# ModulationAnalog.net
KiCad netlist of a schematic drawn in Altium Designer
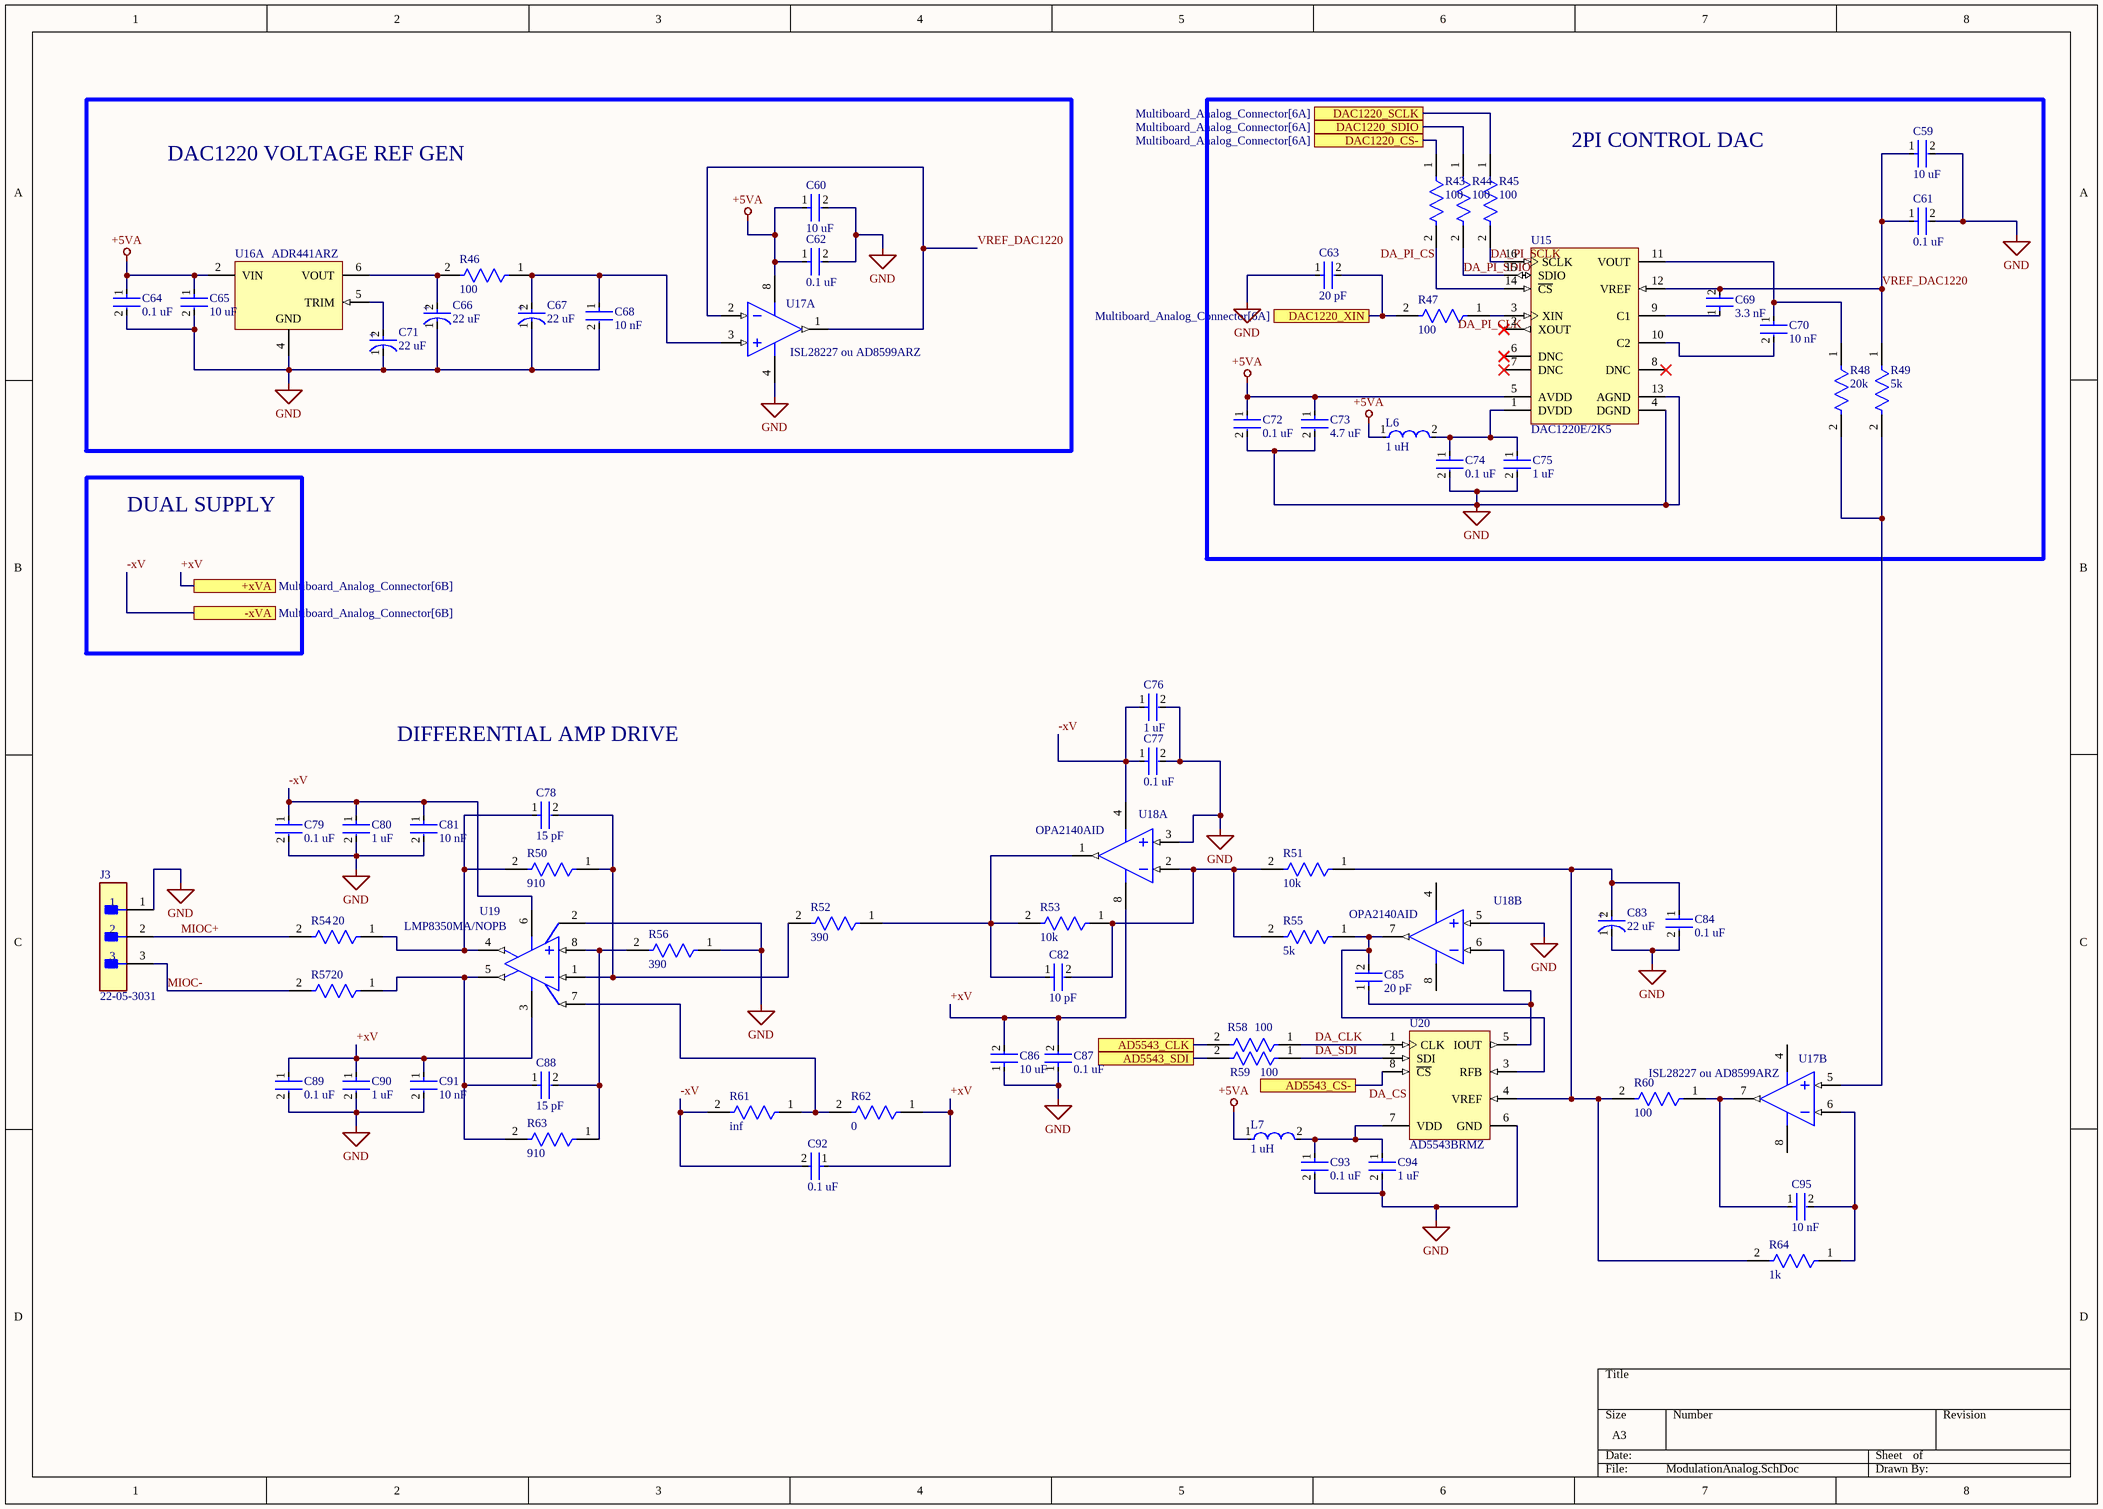
[diagram p0: ModulationAnalog.SchDoc]

(export (version "E")
  (design (tool "Eeschema 10.0.6"))
  (components
    (comp (ref "C59")
      (value "10 uF")
      (footprint "FP-CC0805-0_85-MFG")
      (description "CAP CER 0.1UF 25V X7R 0805")
      (fields (field (name "MANUFACTURER PART NUMBER") "CC0805KRX7R8BB104") (field (name "TOLERANCE") "0.1"))
      (libsource (lib "Altium Content Vault") (part "11868f565c42a9108669ba33697ecf6"))
    )
    (comp (ref "C60")
      (value "10 uF")
      (footprint "FP-CC0805-0_85-MFG")
      (description "CAP CER 0.1UF 25V X7R 0805")
      (fields (field (name "MANUFACTURER PART NUMBER") "CC0805KRX7R8BB104") (field (name "TOLERANCE") "0.1"))
      (libsource (lib "Altium Content Vault") (part "11868f565c42a9108669ba33697ecf6"))
    )
    (comp (ref "C61")
      (value "0.1 uF")
      (footprint "FP-CC0805-0_85-MFG")
      (description "CAP CER 0.1UF 25V X7R 0805")
      (fields (field (name "MANUFACTURER PART NUMBER") "CC0805KRX7R8BB104") (field (name "TOLERANCE") "0.1"))
      (libsource (lib "Altium Content Vault") (part "11868f565c42a9108669ba33697ecf6"))
    )
    (comp (ref "C62")
      (value "0.1 uF")
      (footprint "FP-CC0805-0_85-MFG")
      (description "CAP CER 0.1UF 25V X7R 0805")
      (fields (field (name "MANUFACTURER PART NUMBER") "CC0805KRX7R8BB104") (field (name "TOLERANCE") "0.1"))
      (libsource (lib "Altium Content Vault") (part "11868f565c42a9108669ba33697ecf6"))
    )
    (comp (ref "C63")
      (value "20 pF")
      (footprint "FP-CC0805-0_85-MFG")
      (description "CAP CER 0.1UF 25V X7R 0805")
      (fields (field (name "MANUFACTURER PART NUMBER") "CC0805KRX7R8BB104") (field (name "TOLERANCE") "0.1"))
      (libsource (lib "Altium Content Vault") (part "11868f565c42a9108669ba33697ecf6"))
    )
    (comp (ref "C64")
      (value "0.1 uF")
      (footprint "FP-CC0805-0_85-MFG")
      (description "CAP CER 0.1UF 25V X7R 0805")
      (fields (field (name "MANUFACTURER PART NUMBER") "CC0805KRX7R8BB104") (field (name "TOLERANCE") "0.1"))
      (libsource (lib "Altium Content Vault") (part "11868f565c42a9108669ba33697ecf6"))
    )
    (comp (ref "C65")
      (value "10 uF")
      (footprint "FP-CC0805-0_85-MFG")
      (description "CAP CER 0.1UF 25V X7R 0805")
      (fields (field (name "MANUFACTURER PART NUMBER") "CC0805KRX7R8BB104") (field (name "TOLERANCE") "0.1"))
      (libsource (lib "Altium Content Vault") (part "11868f565c42a9108669ba33697ecf6"))
    )
    (comp (ref "C66")
      (value "22 uF")
      (footprint "FP-TAJP-MFG")
      (description "10uF 10V  ±20% 6Ω 0805  SMD Tantalum Capacitor")
      (fields (field (name "TOLERANCE") "20%") (field (name "VOLTAGE") "10V"))
      (libsource (lib "Altium Content Vault") (part "a00bbbee19879c290e62620ae7e47b1"))
    )
    (comp (ref "C67")
      (value "22 uF")
      (footprint "FP-TAJP-MFG")
      (description "10uF 10V  ±20% 6Ω 0805  SMD Tantalum Capacitor")
      (fields (field (name "TOLERANCE") "20%") (field (name "VOLTAGE") "10V"))
      (libsource (lib "Altium Content Vault") (part "a00bbbee19879c290e62620ae7e47b1"))
    )
    (comp (ref "C68")
      (value "10 nF")
      (footprint "FP-CC0805-0_85-MFG")
      (description "CAP CER 0.1UF 25V X7R 0805")
      (fields (field (name "MANUFACTURER PART NUMBER") "CC0805KRX7R8BB104") (field (name "TOLERANCE") "0.1"))
      (libsource (lib "Altium Content Vault") (part "11868f565c42a9108669ba33697ecf6"))
    )
    (comp (ref "C69")
      (value "3.3 nF")
      (footprint "FP-CC0805-0_85-MFG")
      (description "CAP CER 0.1UF 25V X7R 0805")
      (fields (field (name "MANUFACTURER PART NUMBER") "CC0805KRX7R8BB104") (field (name "TOLERANCE") "0.1"))
      (libsource (lib "Altium Content Vault") (part "11868f565c42a9108669ba33697ecf6"))
    )
    (comp (ref "C70")
      (value "10 nF")
      (footprint "FP-CC0805-0_85-MFG")
      (description "CAP CER 0.1UF 25V X7R 0805")
      (fields (field (name "MANUFACTURER PART NUMBER") "CC0805KRX7R8BB104") (field (name "TOLERANCE") "0.1"))
      (libsource (lib "Altium Content Vault") (part "11868f565c42a9108669ba33697ecf6"))
    )
    (comp (ref "C71")
      (value "22 uF")
      (footprint "FP-TAJP-MFG")
      (description "10uF 10V  ±20% 6Ω 0805  SMD Tantalum Capacitor")
      (fields (field (name "TOLERANCE") "20%") (field (name "VOLTAGE") "10V"))
      (libsource (lib "Altium Content Vault") (part "a00bbbee19879c290e62620ae7e47b1"))
    )
    (comp (ref "C72")
      (value "0.1 uF")
      (footprint "FP-CC0805-0_85-MFG")
      (description "CAP CER 0.1UF 25V X7R 0805")
      (fields (field (name "MANUFACTURER PART NUMBER") "CC0805KRX7R8BB104") (field (name "TOLERANCE") "0.1"))
      (libsource (lib "Altium Content Vault") (part "11868f565c42a9108669ba33697ecf6"))
    )
    (comp (ref "C73")
      (value "4.7 uF")
      (footprint "FP-CC0805-0_85-MFG")
      (description "CAP CER 0.1UF 25V X7R 0805")
      (fields (field (name "MANUFACTURER PART NUMBER") "CC0805KRX7R8BB104") (field (name "TOLERANCE") "0.1"))
      (libsource (lib "Altium Content Vault") (part "11868f565c42a9108669ba33697ecf6"))
    )
    (comp (ref "C74")
      (value "0.1 uF")
      (footprint "FP-CC0805-0_85-MFG")
      (description "CAP CER 0.1UF 25V X7R 0805")
      (fields (field (name "MANUFACTURER PART NUMBER") "CC0805KRX7R8BB104") (field (name "TOLERANCE") "0.1"))
      (libsource (lib "Altium Content Vault") (part "11868f565c42a9108669ba33697ecf6"))
    )
    (comp (ref "C75")
      (value "1 uF")
      (footprint "FP-CC0805-0_85-MFG")
      (description "CAP CER 0.1UF 25V X7R 0805")
      (fields (field (name "MANUFACTURER PART NUMBER") "CC0805KRX7R8BB104") (field (name "TOLERANCE") "0.1"))
      (libsource (lib "Altium Content Vault") (part "11868f565c42a9108669ba33697ecf6"))
    )
    (comp (ref "C76")
      (value "1 uF")
      (footprint "FP-CC0805-0_85-MFG")
      (description "CAP CER 0.1UF 25V X7R 0805")
      (fields (field (name "MANUFACTURER PART NUMBER") "CC0805KRX7R8BB104") (field (name "TOLERANCE") "0.1"))
      (libsource (lib "Altium Content Vault") (part "11868f565c42a9108669ba33697ecf6"))
    )
    (comp (ref "C77")
      (value "0.1 uF")
      (footprint "FP-CC0805-0_85-MFG")
      (description "CAP CER 0.1UF 25V X7R 0805")
      (fields (field (name "MANUFACTURER PART NUMBER") "CC0805KRX7R8BB104") (field (name "TOLERANCE") "0.1"))
      (libsource (lib "Altium Content Vault") (part "11868f565c42a9108669ba33697ecf6"))
    )
    (comp (ref "C78")
      (value "15 pF")
      (footprint "FP-CC0805-0_85-MFG")
      (description "CAP CER 0.1UF 25V X7R 0805")
      (fields (field (name "MANUFACTURER PART NUMBER") "CC0805KRX7R8BB104") (field (name "TOLERANCE") "0.1"))
      (libsource (lib "Altium Content Vault") (part "11868f565c42a9108669ba33697ecf6"))
    )
    (comp (ref "C79")
      (value "0.1 uF")
      (footprint "FP-CC0805-0_85-MFG")
      (description "CAP CER 0.1UF 25V X7R 0805")
      (fields (field (name "MANUFACTURER PART NUMBER") "CC0805KRX7R8BB104") (field (name "TOLERANCE") "0.1"))
      (libsource (lib "Altium Content Vault") (part "11868f565c42a9108669ba33697ecf6"))
    )
    (comp (ref "C80")
      (value "1 uF")
      (footprint "FP-CC0805-0_85-MFG")
      (description "CAP CER 0.1UF 25V X7R 0805")
      (fields (field (name "MANUFACTURER PART NUMBER") "CC0805KRX7R8BB104") (field (name "TOLERANCE") "0.1"))
      (libsource (lib "Altium Content Vault") (part "11868f565c42a9108669ba33697ecf6"))
    )
    (comp (ref "C81")
      (value "10 nF")
      (footprint "FP-CC0805-0_85-MFG")
      (description "CAP CER 0.1UF 25V X7R 0805")
      (fields (field (name "MANUFACTURER PART NUMBER") "CC0805KRX7R8BB104") (field (name "TOLERANCE") "0.1"))
      (libsource (lib "Altium Content Vault") (part "11868f565c42a9108669ba33697ecf6"))
    )
    (comp (ref "C82")
      (value "10 pF")
      (footprint "FP-CC0805-0_85-MFG")
      (description "CAP CER 0.1UF 25V X7R 0805")
      (fields (field (name "MANUFACTURER PART NUMBER") "CC0805KRX7R8BB104") (field (name "TOLERANCE") "0.1"))
      (libsource (lib "Altium Content Vault") (part "11868f565c42a9108669ba33697ecf6"))
    )
    (comp (ref "C83")
      (value "22 uF")
      (footprint "FP-TAJP-MFG")
      (description "10uF 10V  ±20% 6Ω 0805  SMD Tantalum Capacitor")
      (fields (field (name "TOLERANCE") "20%") (field (name "VOLTAGE") "10V"))
      (libsource (lib "Altium Content Vault") (part "a00bbbee19879c290e62620ae7e47b1"))
    )
    (comp (ref "C84")
      (value "0.1 uF")
      (footprint "FP-CC0805-0_85-MFG")
      (description "CAP CER 0.1UF 25V X7R 0805")
      (fields (field (name "MANUFACTURER PART NUMBER") "CC0805KRX7R8BB104") (field (name "TOLERANCE") "0.1"))
      (libsource (lib "Altium Content Vault") (part "11868f565c42a9108669ba33697ecf6"))
    )
    (comp (ref "C85")
      (value "20 pF")
      (footprint "FP-CC0805-0_85-MFG")
      (description "CAP CER 0.1UF 25V X7R 0805")
      (fields (field (name "MANUFACTURER PART NUMBER") "CC0805KRX7R8BB104") (field (name "TOLERANCE") "0.1"))
      (libsource (lib "Altium Content Vault") (part "11868f565c42a9108669ba33697ecf6"))
    )
    (comp (ref "C86")
      (value "10 uF")
      (footprint "FP-CC0805-0_85-MFG")
      (description "CAP CER 0.1UF 25V X7R 0805")
      (fields (field (name "MANUFACTURER PART NUMBER") "CC0805KRX7R8BB104") (field (name "TOLERANCE") "0.1"))
      (libsource (lib "Altium Content Vault") (part "11868f565c42a9108669ba33697ecf6"))
    )
    (comp (ref "C87")
      (value "0.1 uF")
      (footprint "FP-CC0805-0_85-MFG")
      (description "CAP CER 0.1UF 25V X7R 0805")
      (fields (field (name "MANUFACTURER PART NUMBER") "CC0805KRX7R8BB104") (field (name "TOLERANCE") "0.1"))
      (libsource (lib "Altium Content Vault") (part "11868f565c42a9108669ba33697ecf6"))
    )
    (comp (ref "C88")
      (value "15 pF")
      (footprint "FP-CC0805-0_85-MFG")
      (description "CAP CER 0.1UF 25V X7R 0805")
      (fields (field (name "MANUFACTURER PART NUMBER") "CC0805KRX7R8BB104") (field (name "TOLERANCE") "0.1"))
      (libsource (lib "Altium Content Vault") (part "11868f565c42a9108669ba33697ecf6"))
    )
    (comp (ref "C89")
      (value "0.1 uF")
      (footprint "FP-CC0805-0_85-MFG")
      (description "CAP CER 0.1UF 25V X7R 0805")
      (fields (field (name "MANUFACTURER PART NUMBER") "CC0805KRX7R8BB104") (field (name "TOLERANCE") "0.1"))
      (libsource (lib "Altium Content Vault") (part "11868f565c42a9108669ba33697ecf6"))
    )
    (comp (ref "C90")
      (value "1 uF")
      (footprint "FP-CC0805-0_85-MFG")
      (description "CAP CER 0.1UF 25V X7R 0805")
      (fields (field (name "MANUFACTURER PART NUMBER") "CC0805KRX7R8BB104") (field (name "TOLERANCE") "0.1"))
      (libsource (lib "Altium Content Vault") (part "11868f565c42a9108669ba33697ecf6"))
    )
    (comp (ref "C91")
      (value "10 nF")
      (footprint "FP-CC0805-0_85-MFG")
      (description "CAP CER 0.1UF 25V X7R 0805")
      (fields (field (name "MANUFACTURER PART NUMBER") "CC0805KRX7R8BB104") (field (name "TOLERANCE") "0.1"))
      (libsource (lib "Altium Content Vault") (part "11868f565c42a9108669ba33697ecf6"))
    )
    (comp (ref "C92")
      (value "0.1 uF")
      (footprint "FP-CC0805-0_85-MFG")
      (description "CAP CER 0.1UF 25V X7R 0805")
      (fields (field (name "MANUFACTURER PART NUMBER") "CC0805KRX7R8BB104") (field (name "TOLERANCE") "0.1"))
      (libsource (lib "Altium Content Vault") (part "11868f565c42a9108669ba33697ecf6"))
    )
    (comp (ref "C93")
      (value "0.1 uF")
      (footprint "FP-CC0805-0_85-MFG")
      (description "CAP CER 0.1UF 25V X7R 0805")
      (fields (field (name "MANUFACTURER PART NUMBER") "CC0805KRX7R8BB104") (field (name "TOLERANCE") "0.1"))
      (libsource (lib "Altium Content Vault") (part "11868f565c42a9108669ba33697ecf6"))
    )
    (comp (ref "C94")
      (value "1 uF")
      (footprint "FP-CC0805-0_85-MFG")
      (description "CAP CER 0.1UF 25V X7R 0805")
      (fields (field (name "MANUFACTURER PART NUMBER") "CC0805KRX7R8BB104") (field (name "TOLERANCE") "0.1"))
      (libsource (lib "Altium Content Vault") (part "11868f565c42a9108669ba33697ecf6"))
    )
    (comp (ref "C95")
      (value "10 nF")
      (footprint "FP-CC0805-0_85-MFG")
      (description "CAP CER 0.1UF 25V X7R 0805")
      (fields (field (name "MANUFACTURER PART NUMBER") "CC0805KRX7R8BB104") (field (name "TOLERANCE") "0.1"))
      (libsource (lib "Altium Content Vault") (part "11868f565c42a9108669ba33697ecf6"))
    )
    (comp (ref "J3")
      (value "22-05-3031")
      (footprint "FP-22-05-3031-MFG")
      (description "CONN HEADER R/A 3POS 2.54MM")
      (libsource (lib "Altium Content Vault") (part "0d3f023dd272f625e17a2be33dea85f"))
    )
    (comp (ref "L6")
      (value "1 uH")
      (footprint "FP-LQM21DN_00-IPC_B")
      (description "Multilayer Type Inductor for General Circuits, 0805 (2012), 1μH, 10%, 0.4Ω, 50mA")
      (fields (field (name "TOLERANCE") "10%"))
      (libsource (lib "Altium Content Vault") (part "725321dda6339637d4d059423bc1c3c"))
    )
    (comp (ref "L7")
      (value "1 uH")
      (footprint "FP-LQM21DN_00-IPC_B")
      (description "Multilayer Type Inductor for General Circuits, 0805 (2012), 1μH, 10%, 0.4Ω, 50mA")
      (fields (field (name "TOLERANCE") "10%"))
      (libsource (lib "Altium Content Vault") (part "725321dda6339637d4d059423bc1c3c"))
    )
    (comp (ref "R43")
      (value "100")
      (footprint "FP-RR1220-MFG")
      (description "49.9Ω ±0.5% 0.1W 1/10W Chip Resistor 0805 (2012 Metric) Thin Film")
      (fields (field (name "TOLERANCE") "0.5%"))
      (libsource (lib "Altium Content Vault") (part "1029c3af85768c4190bb7ad29bc67b5"))
    )
    (comp (ref "R44")
      (value "100")
      (footprint "FP-RR1220-MFG")
      (description "49.9Ω ±0.5% 0.1W 1/10W Chip Resistor 0805 (2012 Metric) Thin Film")
      (fields (field (name "TOLERANCE") "0.5%"))
      (libsource (lib "Altium Content Vault") (part "1029c3af85768c4190bb7ad29bc67b5"))
    )
    (comp (ref "R45")
      (value "100")
      (footprint "FP-RR1220-MFG")
      (description "49.9Ω ±0.5% 0.1W 1/10W Chip Resistor 0805 (2012 Metric) Thin Film")
      (fields (field (name "TOLERANCE") "0.5%"))
      (libsource (lib "Altium Content Vault") (part "1029c3af85768c4190bb7ad29bc67b5"))
    )
    (comp (ref "R46")
      (value "100")
      (footprint "FP-RR1220-MFG")
      (description "49.9Ω ±0.5% 0.1W 1/10W Chip Resistor 0805 (2012 Metric) Thin Film")
      (fields (field (name "TOLERANCE") "0.5%"))
      (libsource (lib "Altium Content Vault") (part "1029c3af85768c4190bb7ad29bc67b5"))
    )
    (comp (ref "R47")
      (value "100")
      (footprint "FP-RR1220-MFG")
      (description "49.9Ω ±0.5% 0.1W 1/10W Chip Resistor 0805 (2012 Metric) Thin Film")
      (fields (field (name "TOLERANCE") "0.5%"))
      (libsource (lib "Altium Content Vault") (part "1029c3af85768c4190bb7ad29bc67b5"))
    )
    (comp (ref "R48")
      (value "20k")
      (footprint "FP-RR1220-MFG")
      (description "49.9Ω ±0.5% 0.1W 1/10W Chip Resistor 0805 (2012 Metric) Thin Film")
      (fields (field (name "TOLERANCE") "0.5%"))
      (libsource (lib "Altium Content Vault") (part "1029c3af85768c4190bb7ad29bc67b5"))
    )
    (comp (ref "R49")
      (value "5k")
      (footprint "FP-RR1220-MFG")
      (description "49.9Ω ±0.5% 0.1W 1/10W Chip Resistor 0805 (2012 Metric) Thin Film")
      (fields (field (name "TOLERANCE") "0.5%"))
      (libsource (lib "Altium Content Vault") (part "1029c3af85768c4190bb7ad29bc67b5"))
    )
    (comp (ref "R50")
      (value "910")
      (footprint "FP-RR1220-MFG")
      (description "49.9Ω ±0.5% 0.1W 1/10W Chip Resistor 0805 (2012 Metric) Thin Film")
      (fields (field (name "TOLERANCE") "0.5%"))
      (libsource (lib "Altium Content Vault") (part "1029c3af85768c4190bb7ad29bc67b5"))
    )
    (comp (ref "R51")
      (value "10k")
      (footprint "FP-RR1220-MFG")
      (description "49.9Ω ±0.5% 0.1W 1/10W Chip Resistor 0805 (2012 Metric) Thin Film")
      (fields (field (name "TOLERANCE") "0.5%"))
      (libsource (lib "Altium Content Vault") (part "1029c3af85768c4190bb7ad29bc67b5"))
    )
    (comp (ref "R52")
      (value "390")
      (footprint "FP-RR1220-MFG")
      (description "49.9Ω ±0.5% 0.1W 1/10W Chip Resistor 0805 (2012 Metric) Thin Film")
      (fields (field (name "TOLERANCE") "0.5%"))
      (libsource (lib "Altium Content Vault") (part "1029c3af85768c4190bb7ad29bc67b5"))
    )
    (comp (ref "R53")
      (value "10k")
      (footprint "FP-RR1220-MFG")
      (description "49.9Ω ±0.5% 0.1W 1/10W Chip Resistor 0805 (2012 Metric) Thin Film")
      (fields (field (name "TOLERANCE") "0.5%"))
      (libsource (lib "Altium Content Vault") (part "1029c3af85768c4190bb7ad29bc67b5"))
    )
    (comp (ref "R54")
      (value "20")
      (footprint "FP-RR1220-MFG")
      (description "49.9Ω ±0.5% 0.1W 1/10W Chip Resistor 0805 (2012 Metric) Thin Film")
      (fields (field (name "TOLERANCE") "0.5%"))
      (libsource (lib "Altium Content Vault") (part "1029c3af85768c4190bb7ad29bc67b5"))
    )
    (comp (ref "R55")
      (value "5k")
      (footprint "FP-RR1220-MFG")
      (description "49.9Ω ±0.5% 0.1W 1/10W Chip Resistor 0805 (2012 Metric) Thin Film")
      (fields (field (name "TOLERANCE") "0.5%"))
      (libsource (lib "Altium Content Vault") (part "1029c3af85768c4190bb7ad29bc67b5"))
    )
    (comp (ref "R56")
      (value "390")
      (footprint "FP-RR1220-MFG")
      (description "49.9Ω ±0.5% 0.1W 1/10W Chip Resistor 0805 (2012 Metric) Thin Film")
      (fields (field (name "TOLERANCE") "0.5%"))
      (libsource (lib "Altium Content Vault") (part "1029c3af85768c4190bb7ad29bc67b5"))
    )
    (comp (ref "R57")
      (value "20")
      (footprint "FP-RR1220-MFG")
      (description "49.9Ω ±0.5% 0.1W 1/10W Chip Resistor 0805 (2012 Metric) Thin Film")
      (fields (field (name "TOLERANCE") "0.5%"))
      (libsource (lib "Altium Content Vault") (part "1029c3af85768c4190bb7ad29bc67b5"))
    )
    (comp (ref "R58")
      (value "100")
      (footprint "FP-RR1220-MFG")
      (description "49.9Ω ±0.5% 0.1W 1/10W Chip Resistor 0805 (2012 Metric) Thin Film")
      (fields (field (name "TOLERANCE") "0.5%"))
      (libsource (lib "Altium Content Vault") (part "1029c3af85768c4190bb7ad29bc67b5"))
    )
    (comp (ref "R59")
      (value "100")
      (footprint "FP-RR1220-MFG")
      (description "49.9Ω ±0.5% 0.1W 1/10W Chip Resistor 0805 (2012 Metric) Thin Film")
      (fields (field (name "TOLERANCE") "0.5%"))
      (libsource (lib "Altium Content Vault") (part "1029c3af85768c4190bb7ad29bc67b5"))
    )
    (comp (ref "R60")
      (value "100")
      (footprint "FP-RR1220-MFG")
      (description "49.9Ω ±0.5% 0.1W 1/10W Chip Resistor 0805 (2012 Metric) Thin Film")
      (fields (field (name "TOLERANCE") "0.5%"))
      (libsource (lib "Altium Content Vault") (part "1029c3af85768c4190bb7ad29bc67b5"))
    )
    (comp (ref "R61")
      (value "inf")
      (footprint "FP-RR1220-MFG")
      (description "49.9Ω ±0.5% 0.1W 1/10W Chip Resistor 0805 (2012 Metric) Thin Film")
      (fields (field (name "TOLERANCE") "0.5%"))
      (libsource (lib "Altium Content Vault") (part "1029c3af85768c4190bb7ad29bc67b5"))
    )
    (comp (ref "R62")
      (value "0")
      (footprint "FP-RR1220-MFG")
      (description "49.9Ω ±0.5% 0.1W 1/10W Chip Resistor 0805 (2012 Metric) Thin Film")
      (fields (field (name "TOLERANCE") "0.5%"))
      (libsource (lib "Altium Content Vault") (part "1029c3af85768c4190bb7ad29bc67b5"))
    )
    (comp (ref "R63")
      (value "910")
      (footprint "FP-RR1220-MFG")
      (description "49.9Ω ±0.5% 0.1W 1/10W Chip Resistor 0805 (2012 Metric) Thin Film")
      (fields (field (name "TOLERANCE") "0.5%"))
      (libsource (lib "Altium Content Vault") (part "1029c3af85768c4190bb7ad29bc67b5"))
    )
    (comp (ref "R64")
      (value "1k")
      (footprint "FP-RR1220-MFG")
      (description "49.9Ω ±0.5% 0.1W 1/10W Chip Resistor 0805 (2012 Metric) Thin Film")
      (fields (field (name "TOLERANCE") "0.5%"))
      (libsource (lib "Altium Content Vault") (part "1029c3af85768c4190bb7ad29bc67b5"))
    )
    (comp (ref "U15")
      (value "DAC1220E/2K5")
      (footprint "TI-DBQ16_N")
      (description "20-Bit Delta-Sigma Low Power DAC, -40 to 85 degC, 16-pin SOP (DBQ16), Green (RoHS & no Sb/Br)")
      (fields (field (name "MANUFACTURER") "Texas Instruments"))
      (libsource (lib "Altium Content Vault") (part "TI-DAC1220DBQ16"))
    )
    (comp (ref "U16")
      (value "ADR441ARZ")
      (footprint "ADI-R-8_L")
      (fields (field (name "MANUFACTURER") "Analog Devices"))
      (libsource (lib "Altium Content Vault") (part "ADI-ADR4XX-8"))
    )
    (comp (ref "U17")
      (value "ISL28227 ou AD8599ARZ")
      (footprint "ADI-R-8_M")
      (fields
        (field (name "PARTNUMBER") "AD8599ARZ")
        (field (name "MANUFACTURER") "Analog Devices")
        (field (name "GENERIC PART NUMBER") "AD8599")
      )
      (libsource (lib "Altium Content Vault") (part "ADI-ADA4000-2-X-8"))
    )
    (comp (ref "U18")
      (value "OPA2140AID")
      (footprint "D0008A_N")
      (fields (field (name "MANUFACTURER") "Texas Instruments"))
      (libsource (lib "Altium Content Vault") (part "TI-OPA-8_2"))
    )
    (comp (ref "U19")
      (value "LMP8350MA/NOPB")
      (footprint "D0008A_L")
      (fields (field (name "MANUFACTURER") "Texas Instruments"))
      (libsource (lib "Altium Content Vault") (part "AMP-VGA-LMP8350-8"))
    )
    (comp (ref "U20")
      (value "AD5543BRMZ")
      (footprint "RM-8_N")
      (fields (field (name "GENERIC PART NUMBER") "AD5543") (field (name "MANUFACTURER") "Analog Devices"))
      (libsource (lib "Altium Content Vault") (part "ADI-AD5543-RM-8"))
    )
  )
  (nets
    (net (code "1") (name "+5VA") (class "Default")
      (node (ref "C60") (pin "1") (pinfunction "1_1") (pintype "passive"))
      (node (ref "C62") (pin "1") (pinfunction "1_1") (pintype "passive"))
      (node (ref "C64") (pin "1") (pinfunction "1_1") (pintype "passive"))
      (node (ref "C65") (pin "1") (pinfunction "1_1") (pintype "passive"))
      (node (ref "C72") (pin "1") (pinfunction "1_1") (pintype "passive"))
      (node (ref "C73") (pin "1") (pinfunction "1_1") (pintype "passive"))
      (node (ref "L6") (pin "1") (pinfunction "1_1") (pintype "passive"))
      (node (ref "L7") (pin "1") (pinfunction "1_1") (pintype "passive"))
      (node (ref "U15") (pin "5") (pinfunction "AVDD_5") (pintype "power_in"))
      (node (ref "U16") (pin "2") (pinfunction "VIN_2") (pintype "power_in"))
      (node (ref "U17") (pin "8") (pinfunction "+V_8") (pintype "power_in"))
    )
    (net (code "2") (name "/+xV") (class "Default")
      (node (ref "C86") (pin "2") (pinfunction "2_2") (pintype "passive"))
      (node (ref "C87") (pin "2") (pinfunction "2_2") (pintype "passive"))
      (node (ref "C89") (pin "1") (pinfunction "1_1") (pintype "passive"))
      (node (ref "C90") (pin "1") (pinfunction "1_1") (pintype "passive"))
      (node (ref "C91") (pin "1") (pinfunction "1_1") (pintype "passive"))
      (node (ref "C92") (pin "1") (pinfunction "1_1") (pintype "passive"))
      (node (ref "R62") (pin "1") (pinfunction "1_1") (pintype "passive"))
      (node (ref "U18") (pin "8") (pinfunction "V+_8") (pintype "power_in"))
      (node (ref "U19") (pin "3") (pinfunction "V+_3") (pintype "power_in"))
    )
    (net (code "3") (name "/-xV") (class "Default")
      (node (ref "C76") (pin "1") (pinfunction "1_1") (pintype "passive"))
      (node (ref "C77") (pin "1") (pinfunction "1_1") (pintype "passive"))
      (node (ref "C79") (pin "1") (pinfunction "1_1") (pintype "passive"))
      (node (ref "C80") (pin "1") (pinfunction "1_1") (pintype "passive"))
      (node (ref "C81") (pin "1") (pinfunction "1_1") (pintype "passive"))
      (node (ref "C92") (pin "2") (pinfunction "2_2") (pintype "passive"))
      (node (ref "R61") (pin "2") (pinfunction "2_2") (pintype "passive"))
      (node (ref "U18") (pin "4") (pinfunction "V-_4") (pintype "power_in"))
      (node (ref "U19") (pin "6") (pinfunction "V-_6") (pintype "power_in"))
    )
    (net (code "4") (name "/AD5543_CLK") (class "Default")
      (node (ref "R58") (pin "2") (pinfunction "2_2") (pintype "passive"))
    )
    (net (code "5") (name "/AD5543_SDI") (class "Default")
      (node (ref "R59") (pin "2") (pinfunction "2_2") (pintype "passive"))
    )
    (net (code "6") (name "/DAC1220_CS-") (class "Default")
      (node (ref "R43") (pin "1") (pinfunction "1_1") (pintype "passive"))
    )
    (net (code "7") (name "/DAC1220_SCLK") (class "Default")
      (node (ref "R45") (pin "1") (pinfunction "1_1") (pintype "passive"))
    )
    (net (code "8") (name "/DAC1220_SDIO") (class "Default")
      (node (ref "R44") (pin "1") (pinfunction "1_1") (pintype "passive"))
    )
    (net (code "9") (name "/DAC1220_XIN") (class "Default")
      (node (ref "C63") (pin "2") (pinfunction "2_2") (pintype "passive"))
      (node (ref "R47") (pin "2") (pinfunction "2_2") (pintype "passive"))
    )
    (net (code "10") (name "/DA_CLK") (class "Default")
      (node (ref "R58") (pin "1") (pinfunction "1_1") (pintype "passive"))
      (node (ref "U20") (pin "1") (pinfunction "CLK_1") (pintype "input"))
    )
    (net (code "11") (name "/DA_CS") (class "Default")
      (node (ref "U20") (pin "8") (pinfunction "~{CS}_8") (pintype "input"))
    )
    (net (code "12") (name "/DA_PI_CLK") (class "Default")
      (node (ref "R47") (pin "1") (pinfunction "1_1") (pintype "passive"))
      (node (ref "U15") (pin "3") (pinfunction "XIN_3") (pintype "input"))
    )
    (net (code "13") (name "/DA_PI_CS") (class "Default")
      (node (ref "R43") (pin "2") (pinfunction "2_2") (pintype "passive"))
      (node (ref "U15") (pin "14") (pinfunction "~{CS}_14") (pintype "input"))
    )
    (net (code "14") (name "/DA_PI_SCLK") (class "Default")
      (node (ref "R45") (pin "2") (pinfunction "2_2") (pintype "passive"))
      (node (ref "U15") (pin "16") (pinfunction "SCLK_16") (pintype "input"))
    )
    (net (code "15") (name "/DA_PI_SDIO") (class "Default")
      (node (ref "R44") (pin "2") (pinfunction "2_2") (pintype "passive"))
      (node (ref "U15") (pin "15") (pinfunction "SDIO_15") (pintype "bidirectional"))
    )
    (net (code "16") (name "/DA_SDI") (class "Default")
      (node (ref "R59") (pin "1") (pinfunction "1_1") (pintype "passive"))
      (node (ref "U20") (pin "2") (pinfunction "SDI_2") (pintype "input"))
    )
    (net (code "17") (name "/MIOC+") (class "Default")
      (node (ref "J3") (pin "2") (pinfunction "2_2") (pintype "passive"))
      (node (ref "R54") (pin "2") (pinfunction "2_2") (pintype "passive"))
    )
    (net (code "18") (name "/MIOC-") (class "Default")
      (node (ref "J3") (pin "3") (pinfunction "3_3") (pintype "passive"))
      (node (ref "R57") (pin "2") (pinfunction "2_2") (pintype "passive"))
    )
    (net (code "19") (name "/VREF_DAC1220") (class "Default")
      (node (ref "C59") (pin "1") (pinfunction "1_1") (pintype "passive"))
      (node (ref "C61") (pin "1") (pinfunction "1_1") (pintype "passive"))
      (node (ref "C69") (pin "2") (pinfunction "2_2") (pintype "passive"))
      (node (ref "R49") (pin "1") (pinfunction "1_1") (pintype "passive"))
      (node (ref "U15") (pin "12") (pinfunction "VREF_12") (pintype "input"))
      (node (ref "U17") (pin "1") (pinfunction "OUT_A_1") (pintype "output"))
      (node (ref "U17") (pin "2") (pinfunction "-IN_A_2") (pintype "input"))
    )
    (net (code "20") (name "GND") (class "Default")
      (node (ref "C59") (pin "2") (pinfunction "2_2") (pintype "passive"))
      (node (ref "C60") (pin "2") (pinfunction "2_2") (pintype "passive"))
      (node (ref "C61") (pin "2") (pinfunction "2_2") (pintype "passive"))
      (node (ref "C62") (pin "2") (pinfunction "2_2") (pintype "passive"))
      (node (ref "C63") (pin "1") (pinfunction "1_1") (pintype "passive"))
      (node (ref "C64") (pin "2") (pinfunction "2_2") (pintype "passive"))
      (node (ref "C65") (pin "2") (pinfunction "2_2") (pintype "passive"))
      (node (ref "C66") (pin "1") (pinfunction "C_1") (pintype "passive"))
      (node (ref "C67") (pin "1") (pinfunction "C_1") (pintype "passive"))
      (node (ref "C68") (pin "2") (pinfunction "2_2") (pintype "passive"))
      (node (ref "C71") (pin "1") (pinfunction "C_1") (pintype "passive"))
      (node (ref "C72") (pin "2") (pinfunction "2_2") (pintype "passive"))
      (node (ref "C73") (pin "2") (pinfunction "2_2") (pintype "passive"))
      (node (ref "C74") (pin "2") (pinfunction "2_2") (pintype "passive"))
      (node (ref "C75") (pin "2") (pinfunction "2_2") (pintype "passive"))
      (node (ref "C76") (pin "2") (pinfunction "2_2") (pintype "passive"))
      (node (ref "C77") (pin "2") (pinfunction "2_2") (pintype "passive"))
      (node (ref "C79") (pin "2") (pinfunction "2_2") (pintype "passive"))
      (node (ref "C80") (pin "2") (pinfunction "2_2") (pintype "passive"))
      (node (ref "C81") (pin "2") (pinfunction "2_2") (pintype "passive"))
      (node (ref "C83") (pin "1") (pinfunction "C_1") (pintype "passive"))
      (node (ref "C84") (pin "2") (pinfunction "2_2") (pintype "passive"))
      (node (ref "C86") (pin "1") (pinfunction "1_1") (pintype "passive"))
      (node (ref "C87") (pin "1") (pinfunction "1_1") (pintype "passive"))
      (node (ref "C89") (pin "2") (pinfunction "2_2") (pintype "passive"))
      (node (ref "C90") (pin "2") (pinfunction "2_2") (pintype "passive"))
      (node (ref "C91") (pin "2") (pinfunction "2_2") (pintype "passive"))
      (node (ref "C93") (pin "2") (pinfunction "2_2") (pintype "passive"))
      (node (ref "C94") (pin "2") (pinfunction "2_2") (pintype "passive"))
      (node (ref "J3") (pin "1") (pinfunction "1_1") (pintype "passive"))
      (node (ref "R56") (pin "1") (pinfunction "1_1") (pintype "passive"))
      (node (ref "U15") (pin "13") (pinfunction "AGND_13") (pintype "power_in"))
      (node (ref "U15") (pin "4") (pinfunction "DGND_4") (pintype "power_in"))
      (node (ref "U16") (pin "4") (pinfunction "GND_4") (pintype "power_in"))
      (node (ref "U17") (pin "4") (pinfunction "-V_4") (pintype "power_in"))
      (node (ref "U18") (pin "3") (pinfunction "IN_A+_3") (pintype "input"))
      (node (ref "U18") (pin "5") (pinfunction "IN_B+_5") (pintype "input"))
      (node (ref "U19") (pin "2") (pinfunction "VOCM_2") (pintype "passive"))
      (node (ref "U20") (pin "6") (pinfunction "GND_6") (pintype "power_in"))
    )
    (net (code "21") (name "Net-(C66-A)") (class "Default")
      (node (ref "C66") (pin "2") (pinfunction "A_2") (pintype "passive"))
      (node (ref "R46") (pin "2") (pinfunction "2_2") (pintype "passive"))
      (node (ref "U16") (pin "6") (pinfunction "VOUT_6") (pintype "power_in"))
    )
    (net (code "22") (name "Net-(C67-A)") (class "Default")
      (node (ref "C67") (pin "2") (pinfunction "A_2") (pintype "passive"))
      (node (ref "C68") (pin "1") (pinfunction "1_1") (pintype "passive"))
      (node (ref "R46") (pin "1") (pinfunction "1_1") (pintype "passive"))
      (node (ref "U17") (pin "3") (pinfunction "+IN_A_3") (pintype "input"))
    )
    (net (code "23") (name "Net-(C71-A)") (class "Default")
      (node (ref "C71") (pin "2") (pinfunction "A_2") (pintype "passive"))
      (node (ref "U16") (pin "5") (pinfunction "TRIM_5") (pintype "input"))
    )
    (net (code "24") (name "Net-(C83-A)") (class "Default")
      (node (ref "C83") (pin "2") (pinfunction "A_2") (pintype "passive"))
      (node (ref "C84") (pin "1") (pinfunction "1_1") (pintype "passive"))
      (node (ref "R51") (pin "1") (pinfunction "1_1") (pintype "passive"))
      (node (ref "R60") (pin "2") (pinfunction "2_2") (pintype "passive"))
      (node (ref "R64") (pin "2") (pinfunction "2_2") (pintype "passive"))
      (node (ref "U20") (pin "4") (pinfunction "VREF_4") (pintype "input"))
    )
    (net (code "25") (name "Net-(U15-C1)") (class "Default")
      (node (ref "C69") (pin "1") (pinfunction "1_1") (pintype "passive"))
      (node (ref "U15") (pin "9") (pinfunction "C1_9") (pintype "passive"))
    )
    (net (code "26") (name "Net-(U15-C2)") (class "Default")
      (node (ref "C70") (pin "2") (pinfunction "2_2") (pintype "passive"))
      (node (ref "U15") (pin "10") (pinfunction "C2_10") (pintype "passive"))
    )
    (net (code "27") (name "Net-(U15-DVDD)") (class "Default")
      (node (ref "C74") (pin "1") (pinfunction "1_1") (pintype "passive"))
      (node (ref "C75") (pin "1") (pinfunction "1_1") (pintype "passive"))
      (node (ref "L6") (pin "2") (pinfunction "2_2") (pintype "passive"))
      (node (ref "U15") (pin "1") (pinfunction "DVDD_1") (pintype "power_in"))
    )
    (net (code "28") (name "Net-(U15-VOUT)") (class "Default")
      (node (ref "C70") (pin "1") (pinfunction "1_1") (pintype "passive"))
      (node (ref "R48") (pin "1") (pinfunction "1_1") (pintype "passive"))
      (node (ref "U15") (pin "11") (pinfunction "VOUT_11") (pintype "tri_state"))
    )
    (net (code "29") (name "Net-(U17B-+IN_B)") (class "Default")
      (node (ref "R48") (pin "2") (pinfunction "2_2") (pintype "passive"))
      (node (ref "R49") (pin "2") (pinfunction "2_2") (pintype "passive"))
      (node (ref "U17") (pin "5") (pinfunction "+IN_B_5") (pintype "input"))
    )
    (net (code "30") (name "Net-(U17B--IN_B)") (class "Default")
      (node (ref "C95") (pin "2") (pinfunction "2_2") (pintype "passive"))
      (node (ref "R64") (pin "1") (pinfunction "1_1") (pintype "passive"))
      (node (ref "U17") (pin "6") (pinfunction "-IN_B_6") (pintype "input"))
    )
    (net (code "31") (name "Net-(U17B-OUT_B)") (class "Default")
      (node (ref "C95") (pin "1") (pinfunction "1_1") (pintype "passive"))
      (node (ref "R60") (pin "1") (pinfunction "1_1") (pintype "passive"))
      (node (ref "U17") (pin "7") (pinfunction "OUT_B_7") (pintype "output"))
    )
    (net (code "32") (name "Net-(U18A-IN_A-)") (class "Default")
      (node (ref "C82") (pin "2") (pinfunction "2_2") (pintype "passive"))
      (node (ref "R51") (pin "2") (pinfunction "2_2") (pintype "passive"))
      (node (ref "R53") (pin "1") (pinfunction "1_1") (pintype "passive"))
      (node (ref "R55") (pin "2") (pinfunction "2_2") (pintype "passive"))
      (node (ref "U18") (pin "2") (pinfunction "IN_A-_2") (pintype "input"))
    )
    (net (code "33") (name "Net-(U18A-OUT_A)") (class "Default")
      (node (ref "C82") (pin "1") (pinfunction "1_1") (pintype "passive"))
      (node (ref "R52") (pin "1") (pinfunction "1_1") (pintype "passive"))
      (node (ref "R53") (pin "2") (pinfunction "2_2") (pintype "passive"))
      (node (ref "U18") (pin "1") (pinfunction "OUT_A_1") (pintype "output"))
    )
    (net (code "34") (name "Net-(U18B-IN_B-)") (class "Default")
      (node (ref "C85") (pin "1") (pinfunction "1_1") (pintype "passive"))
      (node (ref "U18") (pin "6") (pinfunction "IN_B-_6") (pintype "input"))
      (node (ref "U20") (pin "5") (pinfunction "IOUT_5") (pintype "output"))
    )
    (net (code "35") (name "Net-(U18B-OUT_B)") (class "Default")
      (node (ref "C85") (pin "2") (pinfunction "2_2") (pintype "passive"))
      (node (ref "R55") (pin "1") (pinfunction "1_1") (pintype "passive"))
      (node (ref "U18") (pin "7") (pinfunction "OUT_B_7") (pintype "output"))
      (node (ref "U20") (pin "3") (pinfunction "RFB_3") (pintype "input"))
    )
    (net (code "36") (name "Net-(U19-EN)") (class "Default")
      (node (ref "R61") (pin "1") (pinfunction "1_1") (pintype "passive"))
      (node (ref "R62") (pin "2") (pinfunction "2_2") (pintype "passive"))
      (node (ref "U19") (pin "7") (pinfunction "EN_7") (pintype "input"))
    )
    (net (code "37") (name "Net-(U19-IN+)") (class "Default")
      (node (ref "C88") (pin "2") (pinfunction "2_2") (pintype "passive"))
      (node (ref "R56") (pin "2") (pinfunction "2_2") (pintype "passive"))
      (node (ref "R63") (pin "1") (pinfunction "1_1") (pintype "passive"))
      (node (ref "U19") (pin "8") (pinfunction "IN+_8") (pintype "input"))
    )
    (net (code "38") (name "Net-(U19-IN-)") (class "Default")
      (node (ref "C78") (pin "2") (pinfunction "2_2") (pintype "passive"))
      (node (ref "R50") (pin "1") (pinfunction "1_1") (pintype "passive"))
      (node (ref "R52") (pin "2") (pinfunction "2_2") (pintype "passive"))
      (node (ref "U19") (pin "1") (pinfunction "IN-_1") (pintype "input"))
    )
    (net (code "39") (name "Net-(U19-OUT+)") (class "Default")
      (node (ref "C78") (pin "1") (pinfunction "1_1") (pintype "passive"))
      (node (ref "R50") (pin "2") (pinfunction "2_2") (pintype "passive"))
      (node (ref "R54") (pin "1") (pinfunction "1_1") (pintype "passive"))
      (node (ref "U19") (pin "4") (pinfunction "OUT+_4") (pintype "output"))
    )
    (net (code "40") (name "Net-(U19-OUT-)") (class "Default")
      (node (ref "C88") (pin "1") (pinfunction "1_1") (pintype "passive"))
      (node (ref "R57") (pin "1") (pinfunction "1_1") (pintype "passive"))
      (node (ref "R63") (pin "2") (pinfunction "2_2") (pintype "passive"))
      (node (ref "U19") (pin "5") (pinfunction "OUT-_5") (pintype "output"))
    )
    (net (code "41") (name "Net-(U20-VDD)") (class "Default")
      (node (ref "C93") (pin "1") (pinfunction "1_1") (pintype "passive"))
      (node (ref "C94") (pin "1") (pinfunction "1_1") (pintype "passive"))
      (node (ref "L7") (pin "2") (pinfunction "2_2") (pintype "passive"))
      (node (ref "U20") (pin "7") (pinfunction "VDD_7") (pintype "power_in"))
    )
    (net (code "42") (name "unconnected-(U15-DNC-Pad6)") (class "Default")
      (node (ref "U15") (pin "6") (pinfunction "DNC_6") (pintype "passive+no_connect"))
    )
    (net (code "43") (name "unconnected-(U15-DNC-Pad7)") (class "Default")
      (node (ref "U15") (pin "7") (pinfunction "DNC_7") (pintype "passive+no_connect"))
    )
    (net (code "44") (name "unconnected-(U15-DNC-Pad8)") (class "Default")
      (node (ref "U15") (pin "8") (pinfunction "DNC_8") (pintype "passive+no_connect"))
    )
    (net (code "45") (name "unconnected-(U15-XOUT-Pad2)") (class "Default")
      (node (ref "U15") (pin "2") (pinfunction "XOUT_2") (pintype "output+no_connect"))
    )
    (net (code "46") (name "unconnected-(U17B-+V-Pad8)") (class "Default")
      (node (ref "U17") (pin "8") (pinfunction "+V_8") (pintype "power_in"))
    )
    (net (code "47") (name "unconnected-(U17B--V-Pad4)") (class "Default")
      (node (ref "U17") (pin "4") (pinfunction "-V_4") (pintype "power_in"))
    )
    (net (code "48") (name "unconnected-(U18B-V+-Pad8)") (class "Default")
      (node (ref "U18") (pin "8") (pinfunction "V+_8") (pintype "power_in"))
    )
    (net (code "49") (name "unconnected-(U18B-V--Pad4)") (class "Default")
      (node (ref "U18") (pin "4") (pinfunction "V-_4") (pintype "power_in"))
    )
  )
)
